# dragon_fractal_pcb.net
KiCad netlist of a schematic drawn in EAGLE
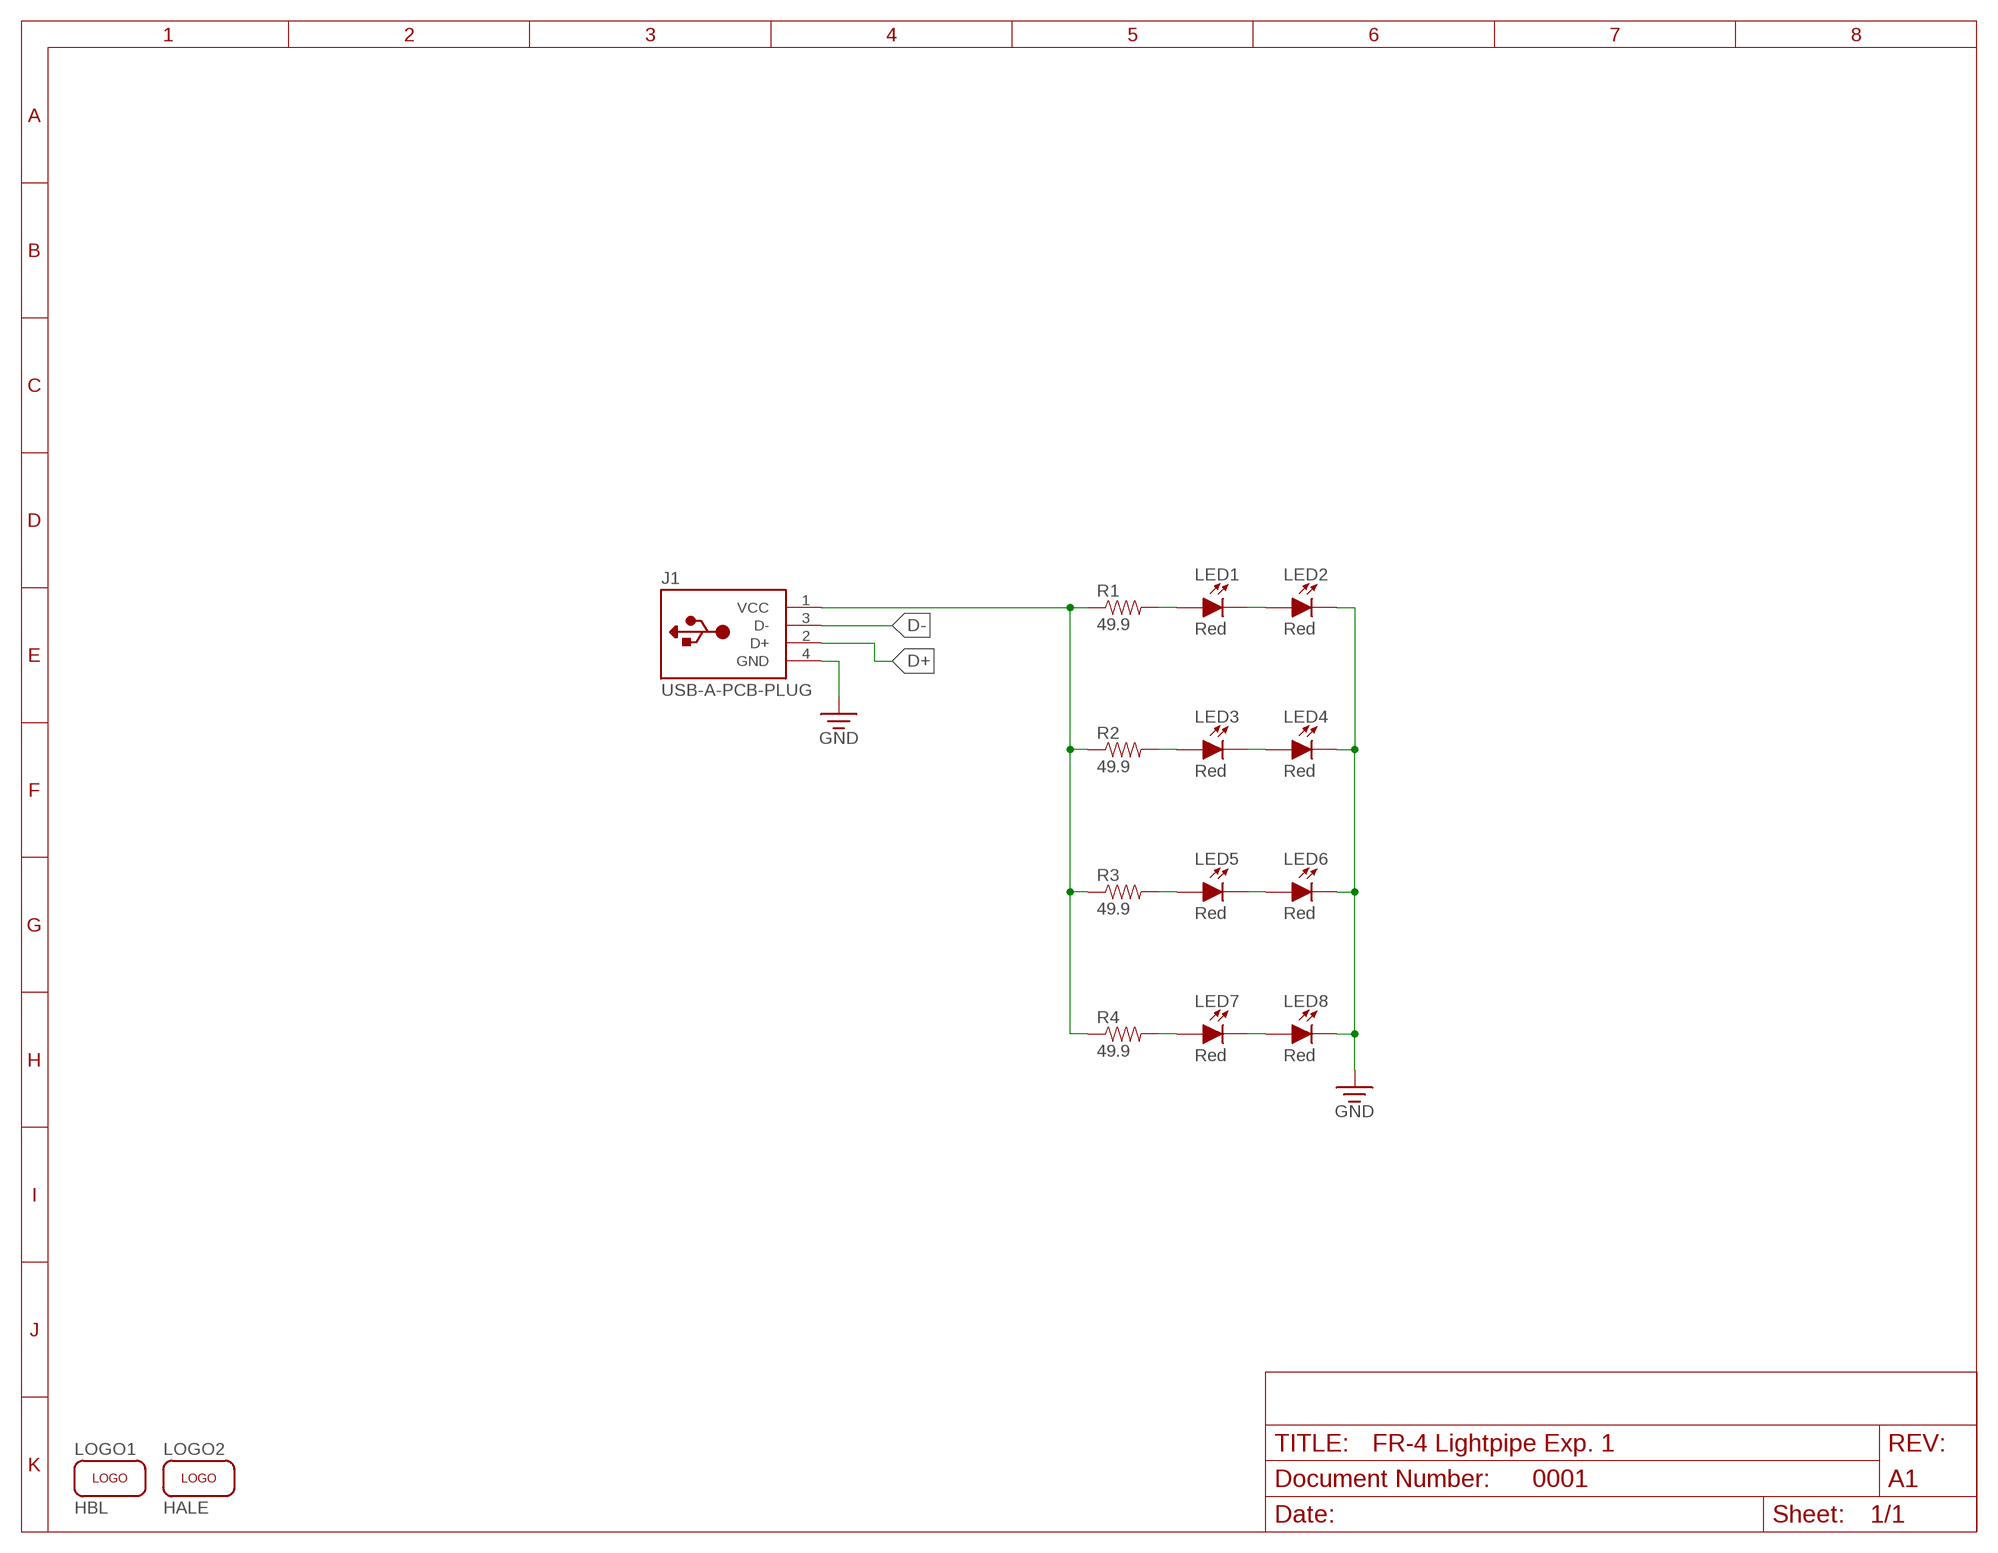
[diagram p0: schematic, sheet 1]

(export (version "E")
  (design (tool "Eeschema 10.0.6"))
  (components
    (comp (ref "J1")
      (value "USB-A-PCB-PLUG")
      (footprint "eagle-import:USB-A-PLUG-PCB")
      (libsource (lib "eagle-import") (part "USB-A-PCB-PLUG"))
    )
    (comp (ref "LED1")
      (value "Red")
      (footprint "eagle-import:LED-TH-OREO")
      (fields
        (field (name "DIGIKEY") "160-1436-1-ND")
        (field (name "MFG") "Lite-On Inc.")
        (field (name "PN") "LTST-C190KRKT")
      )
      (libsource (lib "eagle-import") (part "LED-OREO"))
    )
    (comp (ref "LED2")
      (value "Red")
      (footprint "eagle-import:LED-TH-OREO")
      (fields
        (field (name "DIGIKEY") "160-1436-1-ND")
        (field (name "MFG") "Lite-On Inc.")
        (field (name "PN") "LTST-C190KRKT")
      )
      (libsource (lib "eagle-import") (part "LED-OREO"))
    )
    (comp (ref "LED3")
      (value "Red")
      (footprint "eagle-import:LED-TH-OREO")
      (fields
        (field (name "DIGIKEY") "160-1436-1-ND")
        (field (name "MFG") "Lite-On Inc.")
        (field (name "PN") "LTST-C190KRKT")
      )
      (libsource (lib "eagle-import") (part "LED-OREO"))
    )
    (comp (ref "LED4")
      (value "Red")
      (footprint "eagle-import:LED-TH-OREO")
      (fields
        (field (name "DIGIKEY") "160-1436-1-ND")
        (field (name "MFG") "Lite-On Inc.")
        (field (name "PN") "LTST-C190KRKT")
      )
      (libsource (lib "eagle-import") (part "LED-OREO"))
    )
    (comp (ref "LED5")
      (value "Red")
      (footprint "eagle-import:LED-TH-OREO")
      (fields
        (field (name "DIGIKEY") "160-1436-1-ND")
        (field (name "MFG") "Lite-On Inc.")
        (field (name "PN") "LTST-C190KRKT")
      )
      (libsource (lib "eagle-import") (part "LED-OREO"))
    )
    (comp (ref "LED6")
      (value "Red")
      (footprint "eagle-import:LED-TH-OREO")
      (fields
        (field (name "DIGIKEY") "160-1436-1-ND")
        (field (name "MFG") "Lite-On Inc.")
        (field (name "PN") "LTST-C190KRKT")
      )
      (libsource (lib "eagle-import") (part "LED-OREO"))
    )
    (comp (ref "LED7")
      (value "Red")
      (footprint "eagle-import:LED-TH-OREO")
      (fields
        (field (name "DIGIKEY") "160-1436-1-ND")
        (field (name "MFG") "Lite-On Inc.")
        (field (name "PN") "LTST-C190KRKT")
      )
      (libsource (lib "eagle-import") (part "LED-OREO"))
    )
    (comp (ref "LED8")
      (value "Red")
      (footprint "eagle-import:LED-TH-OREO")
      (fields
        (field (name "DIGIKEY") "160-1436-1-ND")
        (field (name "MFG") "Lite-On Inc.")
        (field (name "PN") "LTST-C190KRKT")
      )
      (libsource (lib "eagle-import") (part "LED-OREO"))
    )
    (comp (ref "LOGO1")
      (value "HBL")
      (footprint "eagle-import:HACKERBOT-SILK-ICON")
      (libsource (lib "eagle-import") (part "LOGO-HACKERBOT"))
    )
    (comp (ref "LOGO2")
      (value "HALE")
      (footprint "eagle-import:HALE-SILK-ICON")
      (libsource (lib "eagle-import") (part "LOGO-HALE"))
    )
    (comp (ref "R1")
      (value "49.9")
      (footprint "eagle-import:0603-NONPOLAR")
      (fields
        (field (name "DIGIKEY") "P49.9HCT-ND")
        (field (name "MFG") "Panasonic")
        (field (name "PN") "ERJ-3EKF49R9V")
      )
      (libsource (lib "eagle-import") (part "R-0603"))
    )
    (comp (ref "R2")
      (value "49.9")
      (footprint "eagle-import:0603-NONPOLAR")
      (fields
        (field (name "DIGIKEY") "P49.9HCT-ND")
        (field (name "MFG") "Panasonic")
        (field (name "PN") "ERJ-3EKF49R9V")
      )
      (libsource (lib "eagle-import") (part "R-0603"))
    )
    (comp (ref "R3")
      (value "49.9")
      (footprint "eagle-import:0603-NONPOLAR")
      (fields
        (field (name "DIGIKEY") "P49.9HCT-ND")
        (field (name "MFG") "Panasonic")
        (field (name "PN") "ERJ-3EKF49R9V")
      )
      (libsource (lib "eagle-import") (part "R-0603"))
    )
    (comp (ref "R4")
      (value "49.9")
      (footprint "eagle-import:0603-NONPOLAR")
      (fields
        (field (name "DIGIKEY") "P49.9HCT-ND")
        (field (name "MFG") "Panasonic")
        (field (name "PN") "ERJ-3EKF49R9V")
      )
      (libsource (lib "eagle-import") (part "R-0603"))
    )
    (comp (ref "U$1")
      (value "FRAME-8.5X11-LANDSCAPE-LET")
      (footprint "eagle-import:FRAME-8.5X11-LANDSCAPE")
      (fields (field (name "DOCNUM") "0001") (field (name "TITLE") "FR-4 Lightpipe Exp. 1"))
      (libsource (lib "eagle-import") (part "FRAME-8.5X11-LANDSCAPE-LET"))
    )
  )
  (nets
    (net (code "1") (name "D+") (class "Default")
      (node (ref "J1") (pin "2") (pinfunction "D+_2") (pintype "bidirectional"))
    )
    (net (code "2") (name "D-") (class "Default")
      (node (ref "J1") (pin "3") (pinfunction "D-_3") (pintype "bidirectional"))
    )
    (net (code "3") (name "GND") (class "Default")
      (node (ref "J1") (pin "4") (pinfunction "GND_4") (pintype "power_in"))
      (node (ref "LED2") (pin "C") (pinfunction "C1_C") (pintype "passive"))
      (node (ref "LED4") (pin "C") (pinfunction "C1_C") (pintype "passive"))
      (node (ref "LED6") (pin "C") (pinfunction "C1_C") (pintype "passive"))
      (node (ref "LED8") (pin "C") (pinfunction "C1_C") (pintype "passive"))
    )
    (net (code "4") (name "Net-(J1-VCC)") (class "Default")
      (node (ref "J1") (pin "1") (pinfunction "VCC_1") (pintype "power_in"))
      (node (ref "R1") (pin "1") (pinfunction "1_1") (pintype "passive"))
      (node (ref "R2") (pin "1") (pinfunction "1_1") (pintype "passive"))
      (node (ref "R3") (pin "1") (pinfunction "1_1") (pintype "passive"))
      (node (ref "R4") (pin "1") (pinfunction "1_1") (pintype "passive"))
    )
    (net (code "5") (name "Net-(LED1-A1)") (class "Default")
      (node (ref "LED1") (pin "A") (pinfunction "A1_A") (pintype "passive"))
      (node (ref "R1") (pin "2") (pinfunction "2_2") (pintype "passive"))
    )
    (net (code "6") (name "Net-(LED1-C1)") (class "Default")
      (node (ref "LED1") (pin "C") (pinfunction "C1_C") (pintype "passive"))
      (node (ref "LED2") (pin "A") (pinfunction "A1_A") (pintype "passive"))
    )
    (net (code "7") (name "Net-(LED3-A1)") (class "Default")
      (node (ref "LED3") (pin "A") (pinfunction "A1_A") (pintype "passive"))
      (node (ref "R2") (pin "2") (pinfunction "2_2") (pintype "passive"))
    )
    (net (code "8") (name "Net-(LED3-C1)") (class "Default")
      (node (ref "LED3") (pin "C") (pinfunction "C1_C") (pintype "passive"))
      (node (ref "LED4") (pin "A") (pinfunction "A1_A") (pintype "passive"))
    )
    (net (code "9") (name "Net-(LED5-A1)") (class "Default")
      (node (ref "LED5") (pin "A") (pinfunction "A1_A") (pintype "passive"))
      (node (ref "R3") (pin "2") (pinfunction "2_2") (pintype "passive"))
    )
    (net (code "10") (name "Net-(LED5-C1)") (class "Default")
      (node (ref "LED5") (pin "C") (pinfunction "C1_C") (pintype "passive"))
      (node (ref "LED6") (pin "A") (pinfunction "A1_A") (pintype "passive"))
    )
    (net (code "11") (name "Net-(LED7-A1)") (class "Default")
      (node (ref "LED7") (pin "A") (pinfunction "A1_A") (pintype "passive"))
      (node (ref "R4") (pin "2") (pinfunction "2_2") (pintype "passive"))
    )
    (net (code "12") (name "Net-(LED7-C1)") (class "Default")
      (node (ref "LED7") (pin "C") (pinfunction "C1_C") (pintype "passive"))
      (node (ref "LED8") (pin "A") (pinfunction "A1_A") (pintype "passive"))
    )
  )
)
